# Raspberry_Pi_PCB.net
KiCad netlist of a schematic drawn in EAGLE
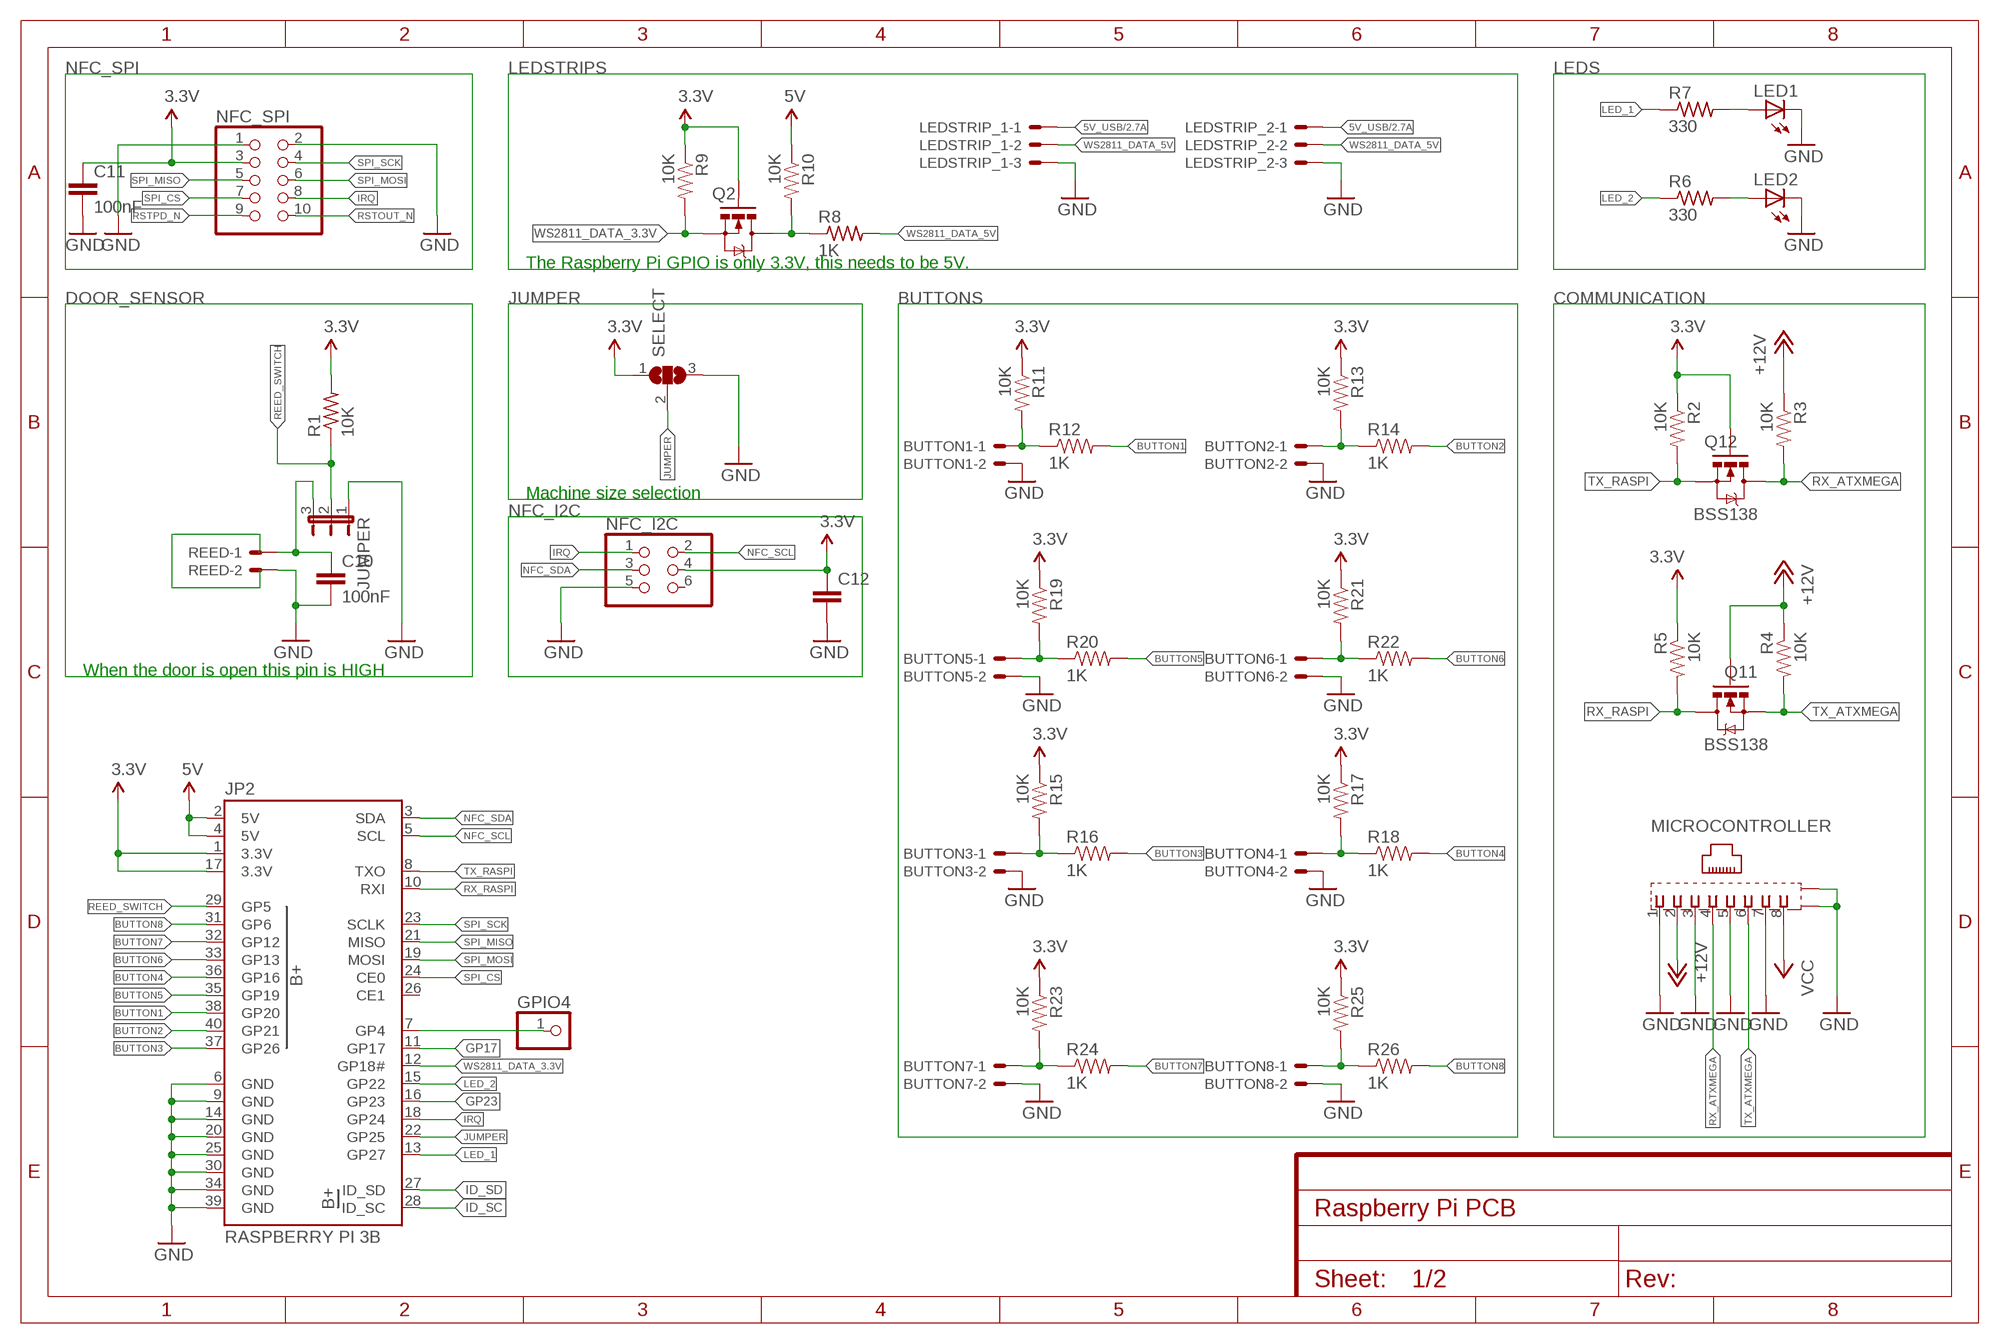
[diagram p0: schematic, sheet 1]
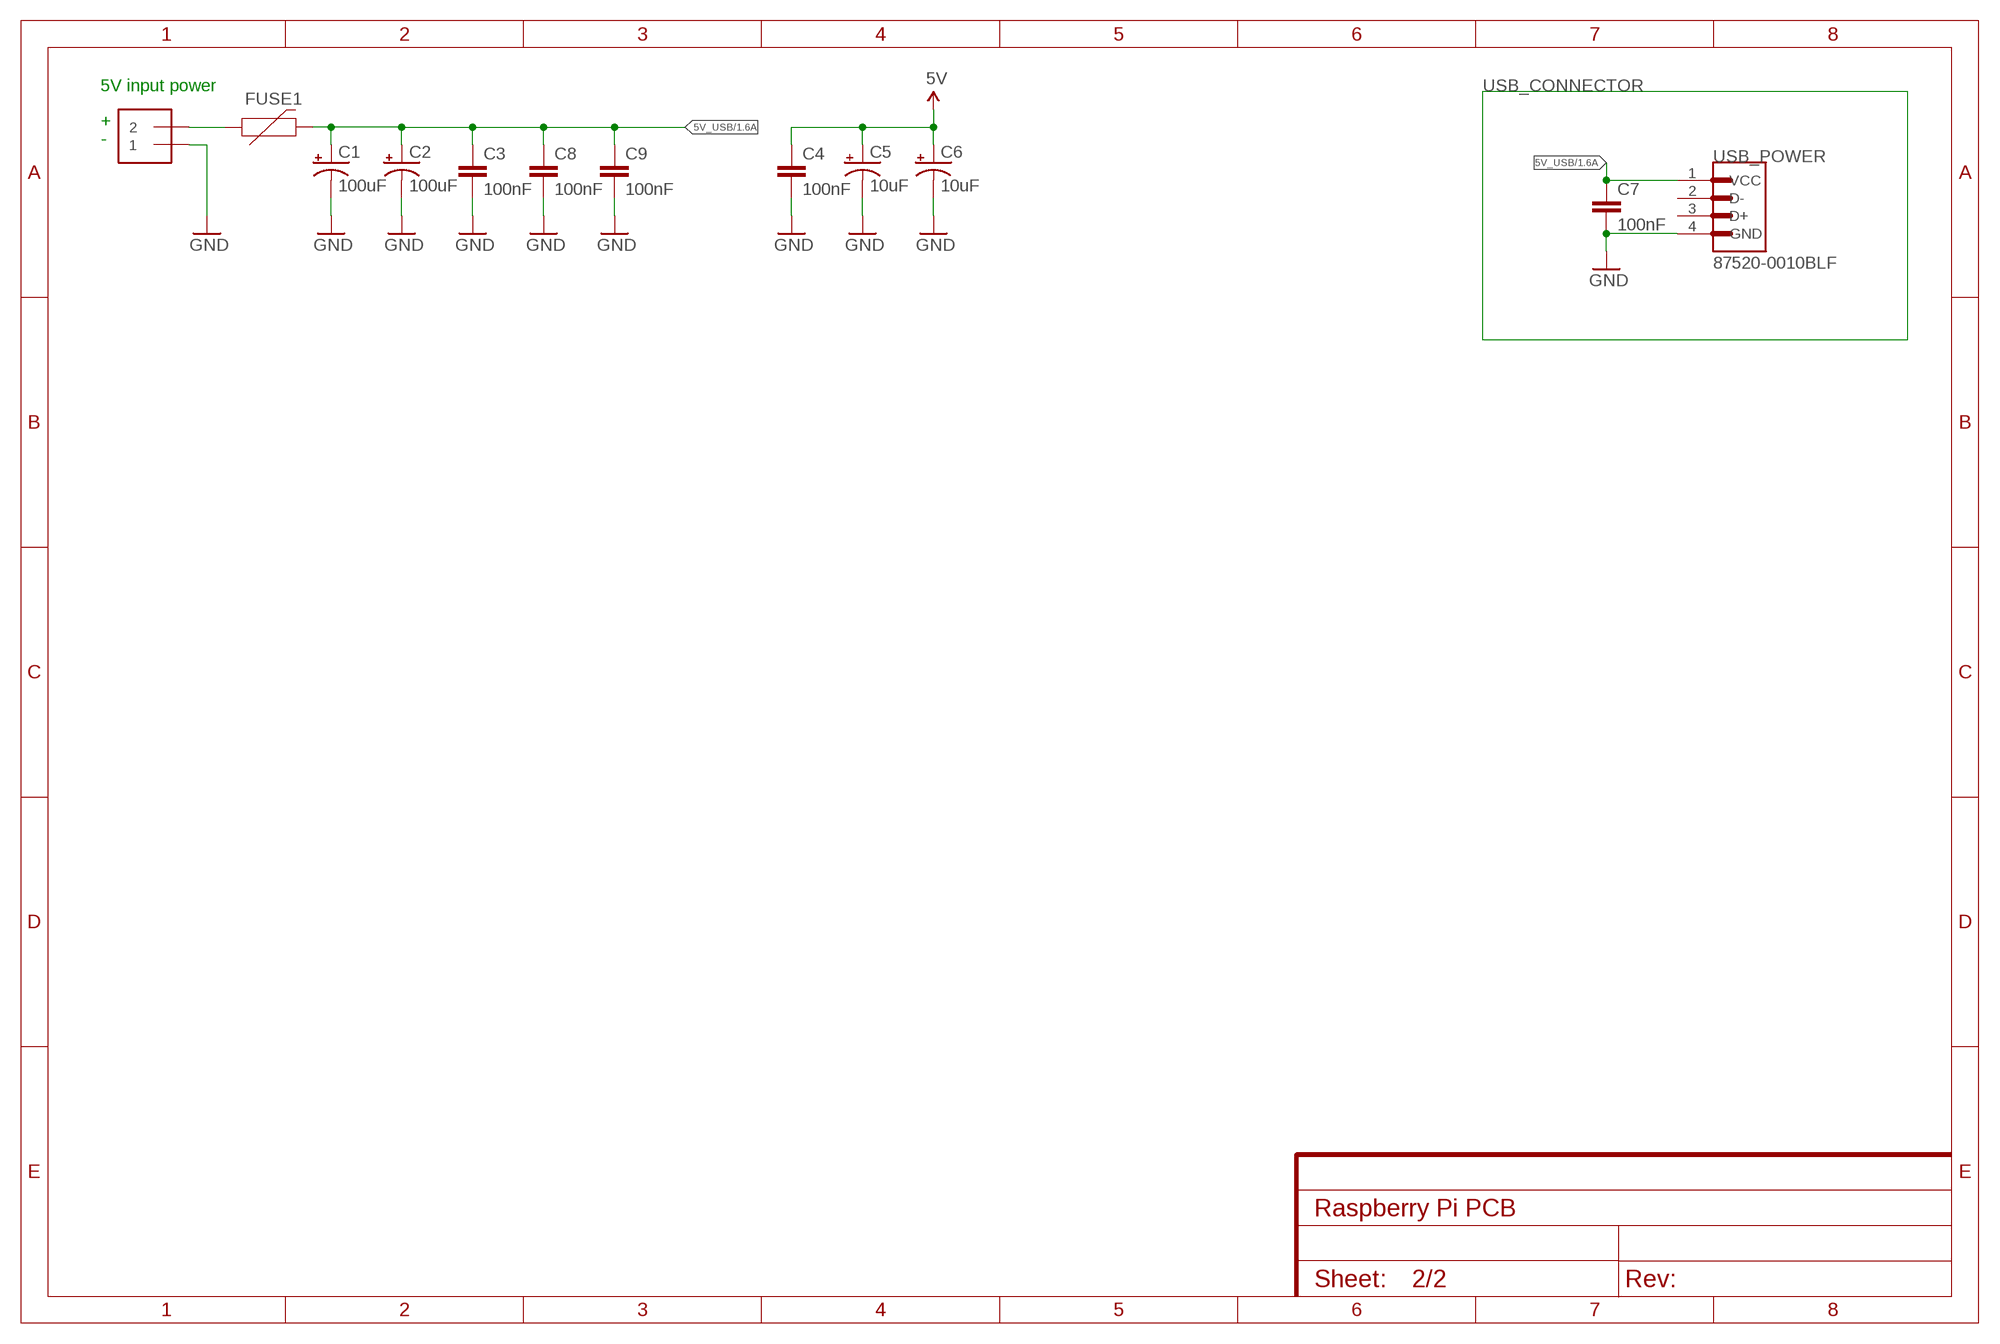
[diagram p1: schematic, sheet 2]

(export (version "E")
  (design (tool "Eeschema 10.0.6"))
  (components
    (comp (ref "BUTTON1")
      (value "22-05-7028-02")
      (footprint "eagle-import:7395-02")
      (fields (field (name "MF") "MOLEX"))
      (libsource (lib "eagle-import") (part "22-?-0205-7028"))
    )
    (comp (ref "BUTTON2")
      (value "22-05-7028-02")
      (footprint "eagle-import:7395-02")
      (fields (field (name "MF") "MOLEX"))
      (libsource (lib "eagle-import") (part "22-?-0205-7028"))
    )
    (comp (ref "BUTTON3")
      (value "22-05-7028-02")
      (footprint "eagle-import:7395-02")
      (fields (field (name "MF") "MOLEX"))
      (libsource (lib "eagle-import") (part "22-?-0205-7028"))
    )
    (comp (ref "BUTTON4")
      (value "22-05-7028-02")
      (footprint "eagle-import:7395-02")
      (fields (field (name "MF") "MOLEX"))
      (libsource (lib "eagle-import") (part "22-?-0205-7028"))
    )
    (comp (ref "BUTTON5")
      (value "22-05-7028-02")
      (footprint "eagle-import:7395-02")
      (fields (field (name "MF") "MOLEX"))
      (libsource (lib "eagle-import") (part "22-?-0205-7028"))
    )
    (comp (ref "BUTTON6")
      (value "22-05-7028-02")
      (footprint "eagle-import:7395-02")
      (fields (field (name "MF") "MOLEX"))
      (libsource (lib "eagle-import") (part "22-?-0205-7028"))
    )
    (comp (ref "BUTTON7")
      (value "22-05-7028-02")
      (footprint "eagle-import:7395-02")
      (fields (field (name "MF") "MOLEX"))
      (libsource (lib "eagle-import") (part "22-?-0205-7028"))
    )
    (comp (ref "BUTTON8")
      (value "22-05-7028-02")
      (footprint "eagle-import:7395-02")
      (fields (field (name "MF") "MOLEX"))
      (libsource (lib "eagle-import") (part "22-?-0205-7028"))
    )
    (comp (ref "C10")
      (value "100nF")
      (footprint "eagle-import:0805")
      (libsource (lib "eagle-import") (part "1.0UF-0805-25V-(+80/-20%)"))
    )
    (comp (ref "C11")
      (value "100nF")
      (footprint "eagle-import:0805")
      (libsource (lib "eagle-import") (part "1.0UF-0805-25V-(+80/-20%)"))
    )
    (comp (ref "C12")
      (value "100nF")
      (footprint "eagle-import:0805")
      (libsource (lib "eagle-import") (part "1.0UF-0805-25V-(+80/-20%)"))
    )
    (comp (ref "GPIO4")
      (value "PINHD-1X1")
      (footprint "eagle-import:1X01")
      (libsource (lib "eagle-import") (part "PINHD-1X1"))
    )
    (comp (ref "JP2")
      (value "RASPBERRY PI 3B")
      (footprint "eagle-import:2X20-SHROUDED")
      (libsource (lib "eagle-import") (part "RASPBERRYPI-B+-GPIO"))
    )
    (comp (ref "JUMPER")
      (value "JP2E")
      (footprint "eagle-import:JP2")
      (libsource (lib "eagle-import") (part "JP2E"))
    )
    (comp (ref "LED1")
      (value "LEDCHIPLED_0805")
      (footprint "eagle-import:CHIPLED_0805")
      (libsource (lib "eagle-import") (part "LEDCHIPLED_0805"))
    )
    (comp (ref "LED2")
      (value "LEDCHIPLED_0805")
      (footprint "eagle-import:CHIPLED_0805")
      (libsource (lib "eagle-import") (part "LEDCHIPLED_0805"))
    )
    (comp (ref "LEDSTRIP_1")
      (value "22-05-7038-03")
      (footprint "eagle-import:7395-03")
      (fields (field (name "MF") "MOLEX"))
      (libsource (lib "eagle-import") (part "22-?-0305-7038"))
    )
    (comp (ref "LEDSTRIP_2")
      (value "22-05-7038-03")
      (footprint "eagle-import:7395-03")
      (fields (field (name "MF") "MOLEX"))
      (libsource (lib "eagle-import") (part "22-?-0305-7038"))
    )
    (comp (ref "MICROCONTROLLER")
      (value "0446200002")
      (footprint "eagle-import:0446200002")
      (fields (field (name "MF") "MOLEX"))
      (libsource (lib "eagle-import") (part "0446200002"))
    )
    (comp (ref "NFC_I2C")
      (value "PINHD-2X3")
      (footprint "eagle-import:2X03")
      (libsource (lib "eagle-import") (part "PINHD-2X3"))
    )
    (comp (ref "NFC_SPI")
      (value "PINHD-2X5")
      (footprint "eagle-import:2X05")
      (libsource (lib "eagle-import") (part "PINHD-2X5"))
    )
    (comp (ref "Q2")
      (value "BSS138")
      (footprint "eagle-import:SOT23-3")
      (libsource (lib "eagle-import") (part "MOSFET-NCHANNELSMD"))
    )
    (comp (ref "Q11")
      (value "BSS138")
      (footprint "eagle-import:SOT23-3")
      (libsource (lib "eagle-import") (part "MOSFET-NCHANNELSMD"))
    )
    (comp (ref "Q12")
      (value "BSS138")
      (footprint "eagle-import:SOT23-3")
      (libsource (lib "eagle-import") (part "MOSFET-NCHANNELSMD"))
    )
    (comp (ref "R1")
      (value "10K")
      (footprint "eagle-import:R0805")
      (libsource (lib "eagle-import") (part "R-US_R0805"))
    )
    (comp (ref "R2")
      (value "10K")
      (footprint "eagle-import:0603-RES")
      (libsource (lib "eagle-import") (part "RESISTOR0603-RES"))
    )
    (comp (ref "R3")
      (value "10K")
      (footprint "eagle-import:0603-RES")
      (libsource (lib "eagle-import") (part "RESISTOR0603-RES"))
    )
    (comp (ref "R4")
      (value "10K")
      (footprint "eagle-import:0603-RES")
      (libsource (lib "eagle-import") (part "RESISTOR0603-RES"))
    )
    (comp (ref "R5")
      (value "10K")
      (footprint "eagle-import:0603-RES")
      (libsource (lib "eagle-import") (part "RESISTOR0603-RES"))
    )
    (comp (ref "R6")
      (value "330")
      (footprint "eagle-import:R0805")
      (libsource (lib "eagle-import") (part "R-US_R0805"))
    )
    (comp (ref "R7")
      (value "330")
      (footprint "eagle-import:R0805")
      (libsource (lib "eagle-import") (part "R-US_R0805"))
    )
    (comp (ref "R8")
      (value "1K")
      (footprint "eagle-import:R0805")
      (libsource (lib "eagle-import") (part "adafruit_420_R-US_R0805"))
    )
    (comp (ref "R9")
      (value "10K")
      (footprint "eagle-import:0603-RES")
      (libsource (lib "eagle-import") (part "RESISTOR0603-RES"))
    )
    (comp (ref "R10")
      (value "10K")
      (footprint "eagle-import:0603-RES")
      (libsource (lib "eagle-import") (part "RESISTOR0603-RES"))
    )
    (comp (ref "R11")
      (value "10K")
      (footprint "eagle-import:0603-RES")
      (libsource (lib "eagle-import") (part "RESISTOR0603-RES"))
    )
    (comp (ref "R12")
      (value "1K")
      (footprint "eagle-import:0603-RES")
      (libsource (lib "eagle-import") (part "RESISTOR0603-RES"))
    )
    (comp (ref "R13")
      (value "10K")
      (footprint "eagle-import:0603-RES")
      (libsource (lib "eagle-import") (part "RESISTOR0603-RES"))
    )
    (comp (ref "R14")
      (value "1K")
      (footprint "eagle-import:0603-RES")
      (libsource (lib "eagle-import") (part "RESISTOR0603-RES"))
    )
    (comp (ref "R15")
      (value "10K")
      (footprint "eagle-import:0603-RES")
      (libsource (lib "eagle-import") (part "RESISTOR0603-RES"))
    )
    (comp (ref "R16")
      (value "1K")
      (footprint "eagle-import:0603-RES")
      (libsource (lib "eagle-import") (part "RESISTOR0603-RES"))
    )
    (comp (ref "R17")
      (value "10K")
      (footprint "eagle-import:0603-RES")
      (libsource (lib "eagle-import") (part "RESISTOR0603-RES"))
    )
    (comp (ref "R18")
      (value "1K")
      (footprint "eagle-import:0603-RES")
      (libsource (lib "eagle-import") (part "RESISTOR0603-RES"))
    )
    (comp (ref "R19")
      (value "10K")
      (footprint "eagle-import:0603-RES")
      (libsource (lib "eagle-import") (part "RESISTOR0603-RES"))
    )
    (comp (ref "R20")
      (value "1K")
      (footprint "eagle-import:0603-RES")
      (libsource (lib "eagle-import") (part "RESISTOR0603-RES"))
    )
    (comp (ref "R21")
      (value "10K")
      (footprint "eagle-import:0603-RES")
      (libsource (lib "eagle-import") (part "RESISTOR0603-RES"))
    )
    (comp (ref "R22")
      (value "1K")
      (footprint "eagle-import:0603-RES")
      (libsource (lib "eagle-import") (part "RESISTOR0603-RES"))
    )
    (comp (ref "R23")
      (value "10K")
      (footprint "eagle-import:0603-RES")
      (libsource (lib "eagle-import") (part "RESISTOR0603-RES"))
    )
    (comp (ref "R24")
      (value "1K")
      (footprint "eagle-import:0603-RES")
      (libsource (lib "eagle-import") (part "RESISTOR0603-RES"))
    )
    (comp (ref "R25")
      (value "10K")
      (footprint "eagle-import:0603-RES")
      (libsource (lib "eagle-import") (part "RESISTOR0603-RES"))
    )
    (comp (ref "R26")
      (value "1K")
      (footprint "eagle-import:0603-RES")
      (libsource (lib "eagle-import") (part "RESISTOR0603-RES"))
    )
    (comp (ref "REED")
      (value "22-05-7028-02")
      (footprint "eagle-import:7395-02")
      (fields (field (name "MF") "MOLEX"))
      (libsource (lib "eagle-import") (part "22-?-0205-7028"))
    )
    (comp (ref "SELECT")
      (value "SJ2W")
      (footprint "eagle-import:SJ_2")
      (libsource (lib "eagle-import") (part "SJ2W"))
    )
    (comp (ref "C1")
      (value "100uF")
      (footprint "eagle-import:175TMP-0810")
      (libsource (lib "eagle-import") (part "CPOL-US175TMP-0810"))
    )
    (comp (ref "C2")
      (value "100uF")
      (footprint "eagle-import:175TMP-0810")
      (libsource (lib "eagle-import") (part "CPOL-US175TMP-0810"))
    )
    (comp (ref "C3")
      (value "100nF")
      (footprint "eagle-import:0805")
      (libsource (lib "eagle-import") (part "1.0UF-0805-25V-(+80/-20%)"))
    )
    (comp (ref "C4")
      (value "100nF")
      (footprint "eagle-import:0805")
      (libsource (lib "eagle-import") (part "1.0UF-0805-25V-(+80/-20%)"))
    )
    (comp (ref "C5")
      (value "10uF")
      (footprint "eagle-import:153CLV-0505")
      (libsource (lib "eagle-import") (part "CPOL-US153CLV-0505"))
    )
    (comp (ref "C6")
      (value "10uF")
      (footprint "eagle-import:153CLV-0505")
      (libsource (lib "eagle-import") (part "CPOL-US153CLV-0505"))
    )
    (comp (ref "C7")
      (value "100nF")
      (footprint "eagle-import:0805")
      (libsource (lib "eagle-import") (part "1.0UF-0805-25V-(+80/-20%)"))
    )
    (comp (ref "C8")
      (value "100nF")
      (footprint "eagle-import:0805")
      (libsource (lib "eagle-import") (part "1.0UF-0805-25V-(+80/-20%)"))
    )
    (comp (ref "C9")
      (value "100nF")
      (footprint "eagle-import:0805")
      (libsource (lib "eagle-import") (part "1.0UF-0805-25V-(+80/-20%)"))
    )
    (comp (ref "FUSE1")
      (value "6V/0.5A")
      (footprint "eagle-import:1206")
      (libsource (lib "eagle-import") (part "PPTC_HALF-AMP"))
    )
    (comp (ref "INPUT")
      (value "1X2-3.5MM")
      (footprint "eagle-import:1X2-3.5MM")
      (libsource (lib "eagle-import") (part "1X2-3.5MM"))
    )
    (comp (ref "USB_POWER")
      (value "87520-0010BLF")
      (footprint "eagle-import:FCI_87520-0010BLF")
      (fields (field (name "DIGI-KEY_PART_NUMBER") "609-1045-ND") (field (name "MF") "Amphenol ICC"))
      (libsource (lib "eagle-import") (part "87520-0010BLF"))
    )
  )
  (nets
    (net (code "1") (name "+12V") (class "Default")
      (node (ref "MICROCONTROLLER") (pin "2") (pinfunction "2_2") (pintype "passive"))
      (node (ref "Q11") (pin "1") (pinfunction "G_1") (pintype "passive"))
      (node (ref "R3") (pin "1") (pinfunction "1_1") (pintype "passive"))
      (node (ref "R4") (pin "1") (pinfunction "1_1") (pintype "passive"))
    )
    (net (code "2") (name "3.3V") (class "Default")
      (node (ref "C11") (pin "1") (pinfunction "1_1") (pintype "passive"))
      (node (ref "C12") (pin "1") (pinfunction "1_1") (pintype "passive"))
      (node (ref "JP2") (pin "1") (pinfunction "3.3V_1") (pintype "power_in"))
      (node (ref "JP2") (pin "17") (pinfunction "3.3V_17") (pintype "power_in"))
      (node (ref "NFC_I2C") (pin "4") (pinfunction "4_4") (pintype "passive"))
      (node (ref "NFC_SPI") (pin "3") (pinfunction "3_3") (pintype "passive"))
      (node (ref "Q12") (pin "1") (pinfunction "G_1") (pintype "passive"))
      (node (ref "Q2") (pin "1") (pinfunction "G_1") (pintype "passive"))
      (node (ref "R1") (pin "2") (pinfunction "2_2") (pintype "passive"))
      (node (ref "R11") (pin "1") (pinfunction "1_1") (pintype "passive"))
      (node (ref "R13") (pin "1") (pinfunction "1_1") (pintype "passive"))
      (node (ref "R15") (pin "1") (pinfunction "1_1") (pintype "passive"))
      (node (ref "R17") (pin "1") (pinfunction "1_1") (pintype "passive"))
      (node (ref "R19") (pin "1") (pinfunction "1_1") (pintype "passive"))
      (node (ref "R2") (pin "1") (pinfunction "1_1") (pintype "passive"))
      (node (ref "R21") (pin "1") (pinfunction "1_1") (pintype "passive"))
      (node (ref "R23") (pin "1") (pinfunction "1_1") (pintype "passive"))
      (node (ref "R25") (pin "1") (pinfunction "1_1") (pintype "passive"))
      (node (ref "R5") (pin "1") (pinfunction "1_1") (pintype "passive"))
      (node (ref "R9") (pin "1") (pinfunction "1_1") (pintype "passive"))
      (node (ref "SELECT") (pin "1") (pinfunction "1_1") (pintype "passive"))
    )
    (net (code "3") (name "5V") (class "Default")
      (node (ref "C4") (pin "1") (pinfunction "1_1") (pintype "passive"))
      (node (ref "C5") (pin "+") (pinfunction "+_+") (pintype "passive"))
      (node (ref "C6") (pin "+") (pinfunction "+_+") (pintype "passive"))
      (node (ref "JP2") (pin "2") (pinfunction "5V_2") (pintype "power_in"))
      (node (ref "JP2") (pin "4") (pinfunction "5V_4") (pintype "power_in"))
      (node (ref "R10") (pin "1") (pinfunction "1_1") (pintype "passive"))
    )
    (net (code "4") (name "5V_USB") (class "Default")
      (node (ref "C1") (pin "+") (pinfunction "+_+") (pintype "passive"))
      (node (ref "C2") (pin "+") (pinfunction "+_+") (pintype "passive"))
      (node (ref "C3") (pin "1") (pinfunction "1_1") (pintype "passive"))
      (node (ref "C7") (pin "1") (pinfunction "1_1") (pintype "passive"))
      (node (ref "C8") (pin "1") (pinfunction "1_1") (pintype "passive"))
      (node (ref "C9") (pin "1") (pinfunction "1_1") (pintype "passive"))
      (node (ref "FUSE1") (pin "2") (pinfunction "2_2") (pintype "bidirectional"))
      (node (ref "LEDSTRIP_1") (pin "1") (pinfunction "S_1") (pintype "passive"))
      (node (ref "LEDSTRIP_2") (pin "1") (pinfunction "S_1") (pintype "passive"))
      (node (ref "USB_POWER") (pin "1") (pinfunction "VCC_1") (pintype "power_in"))
    )
    (net (code "5") (name "BUTTON1") (class "Default")
      (node (ref "JP2") (pin "38") (pinfunction "GP20_38") (pintype "bidirectional"))
      (node (ref "R12") (pin "2") (pinfunction "2_2") (pintype "passive"))
    )
    (net (code "6") (name "BUTTON2") (class "Default")
      (node (ref "JP2") (pin "40") (pinfunction "GP21_40") (pintype "bidirectional"))
      (node (ref "R14") (pin "2") (pinfunction "2_2") (pintype "passive"))
    )
    (net (code "7") (name "BUTTON3") (class "Default")
      (node (ref "JP2") (pin "37") (pinfunction "GP26_37") (pintype "bidirectional"))
      (node (ref "R16") (pin "2") (pinfunction "2_2") (pintype "passive"))
    )
    (net (code "8") (name "BUTTON4") (class "Default")
      (node (ref "JP2") (pin "36") (pinfunction "GP16_36") (pintype "bidirectional"))
      (node (ref "R18") (pin "2") (pinfunction "2_2") (pintype "passive"))
    )
    (net (code "9") (name "BUTTON5") (class "Default")
      (node (ref "JP2") (pin "35") (pinfunction "GP19_35") (pintype "bidirectional"))
      (node (ref "R20") (pin "2") (pinfunction "2_2") (pintype "passive"))
    )
    (net (code "10") (name "BUTTON6") (class "Default")
      (node (ref "JP2") (pin "33") (pinfunction "GP13_33") (pintype "bidirectional"))
      (node (ref "R22") (pin "2") (pinfunction "2_2") (pintype "passive"))
    )
    (net (code "11") (name "BUTTON7") (class "Default")
      (node (ref "JP2") (pin "32") (pinfunction "GP12_32") (pintype "bidirectional"))
      (node (ref "R24") (pin "2") (pinfunction "2_2") (pintype "passive"))
    )
    (net (code "12") (name "BUTTON8") (class "Default")
      (node (ref "JP2") (pin "31") (pinfunction "GP6_31") (pintype "bidirectional"))
      (node (ref "R26") (pin "2") (pinfunction "2_2") (pintype "passive"))
    )
    (net (code "16") (name "GND") (class "Default")
      (node (ref "BUTTON1") (pin "2") (pinfunction "S_2") (pintype "passive"))
      (node (ref "BUTTON2") (pin "2") (pinfunction "S_2") (pintype "passive"))
      (node (ref "BUTTON3") (pin "2") (pinfunction "S_2") (pintype "passive"))
      (node (ref "BUTTON4") (pin "2") (pinfunction "S_2") (pintype "passive"))
      (node (ref "BUTTON5") (pin "2") (pinfunction "S_2") (pintype "passive"))
      (node (ref "BUTTON6") (pin "2") (pinfunction "S_2") (pintype "passive"))
      (node (ref "BUTTON7") (pin "2") (pinfunction "S_2") (pintype "passive"))
      (node (ref "BUTTON8") (pin "2") (pinfunction "S_2") (pintype "passive"))
      (node (ref "C1") (pin "-") (pinfunction "-_-") (pintype "passive"))
      (node (ref "C10") (pin "2") (pinfunction "2_2") (pintype "passive"))
      (node (ref "C11") (pin "2") (pinfunction "2_2") (pintype "passive"))
      (node (ref "C12") (pin "2") (pinfunction "2_2") (pintype "passive"))
      (node (ref "C2") (pin "-") (pinfunction "-_-") (pintype "passive"))
      (node (ref "C3") (pin "2") (pinfunction "2_2") (pintype "passive"))
      (node (ref "C4") (pin "2") (pinfunction "2_2") (pintype "passive"))
      (node (ref "C5") (pin "-") (pinfunction "-_-") (pintype "passive"))
      (node (ref "C6") (pin "-") (pinfunction "-_-") (pintype "passive"))
      (node (ref "C7") (pin "2") (pinfunction "2_2") (pintype "passive"))
      (node (ref "C8") (pin "2") (pinfunction "2_2") (pintype "passive"))
      (node (ref "C9") (pin "2") (pinfunction "2_2") (pintype "passive"))
      (node (ref "INPUT") (pin "1") (pinfunction "1_1") (pintype "passive"))
      (node (ref "JP2") (pin "14") (pinfunction "GND_14") (pintype "power_in"))
      (node (ref "JP2") (pin "20") (pinfunction "GND_20") (pintype "power_in"))
      (node (ref "JP2") (pin "25") (pinfunction "GND_25") (pintype "power_in"))
      (node (ref "JP2") (pin "30") (pinfunction "GND_30") (pintype "power_in"))
      (node (ref "JP2") (pin "34") (pinfunction "GND_34") (pintype "power_in"))
      (node (ref "JP2") (pin "39") (pinfunction "GND_39") (pintype "power_in"))
      (node (ref "JP2") (pin "6") (pinfunction "GND_6") (pintype "power_in"))
      (node (ref "JP2") (pin "9") (pinfunction "GND_9") (pintype "power_in"))
      (node (ref "JUMPER") (pin "1") (pinfunction "1_1") (pintype "passive"))
      (node (ref "LED1") (pin "C") (pinfunction "C_C") (pintype "passive"))
      (node (ref "LED2") (pin "C") (pinfunction "C_C") (pintype "passive"))
      (node (ref "LEDSTRIP_1") (pin "3") (pinfunction "S_3") (pintype "passive"))
      (node (ref "LEDSTRIP_2") (pin "3") (pinfunction "S_3") (pintype "passive"))
      (node (ref "MICROCONTROLLER") (pin "1") (pinfunction "1_1") (pintype "passive"))
      (node (ref "MICROCONTROLLER") (pin "3") (pinfunction "3_3") (pintype "passive"))
      (node (ref "MICROCONTROLLER") (pin "5") (pinfunction "5_5") (pintype "passive"))
      (node (ref "MICROCONTROLLER") (pin "7") (pinfunction "7_7") (pintype "passive"))
      (node (ref "MICROCONTROLLER") (pin "S@1") (pinfunction "S1_S@1") (pintype "passive"))
      (node (ref "MICROCONTROLLER") (pin "S@2") (pinfunction "S2_S@2") (pintype "passive"))
      (node (ref "NFC_I2C") (pin "5") (pinfunction "5_5") (pintype "passive"))
      (node (ref "NFC_SPI") (pin "1") (pinfunction "1_1") (pintype "passive"))
      (node (ref "NFC_SPI") (pin "2") (pinfunction "2_2") (pintype "passive"))
      (node (ref "REED") (pin "2") (pinfunction "S_2") (pintype "passive"))
      (node (ref "SELECT") (pin "3") (pinfunction "3_3") (pintype "passive"))
      (node (ref "USB_POWER") (pin "4") (pinfunction "GND_4") (pintype "power_in"))
    )
    (net (code "17") (name "GP17") (class "Default")
      (node (ref "JP2") (pin "11") (pinfunction "GP17_11") (pintype "bidirectional"))
    )
    (net (code "18") (name "GP23") (class "Default")
      (node (ref "JP2") (pin "16") (pinfunction "GP23_16") (pintype "bidirectional"))
    )
    (net (code "19") (name "ID_SC") (class "Default")
      (node (ref "JP2") (pin "28") (pinfunction "ID_SC_28") (pintype "bidirectional"))
    )
    (net (code "20") (name "ID_SD") (class "Default")
      (node (ref "JP2") (pin "27") (pinfunction "ID_SD_27") (pintype "bidirectional"))
    )
    (net (code "21") (name "IRQ") (class "Default")
      (node (ref "JP2") (pin "18") (pinfunction "GP24_18") (pintype "bidirectional"))
      (node (ref "NFC_I2C") (pin "1") (pinfunction "1_1") (pintype "passive"))
      (node (ref "NFC_SPI") (pin "8") (pinfunction "8_8") (pintype "passive"))
    )
    (net (code "22") (name "JUMPER") (class "Default")
      (node (ref "JP2") (pin "22") (pinfunction "GP25_22") (pintype "bidirectional"))
      (node (ref "SELECT") (pin "2") (pinfunction "2_2") (pintype "passive"))
    )
    (net (code "25") (name "LED_1") (class "Default")
      (node (ref "JP2") (pin "13") (pinfunction "GP27_13") (pintype "bidirectional"))
      (node (ref "R7") (pin "1") (pinfunction "1_1") (pintype "passive"))
    )
    (net (code "26") (name "LED_2") (class "Default")
      (node (ref "JP2") (pin "15") (pinfunction "GP22_15") (pintype "bidirectional"))
      (node (ref "R6") (pin "1") (pinfunction "1_1") (pintype "passive"))
    )
    (net (code "28") (name "NFC_SCL") (class "Default")
      (node (ref "JP2") (pin "5") (pinfunction "SCL_5") (pintype "bidirectional"))
      (node (ref "NFC_I2C") (pin "2") (pinfunction "2_2") (pintype "passive"))
    )
    (net (code "29") (name "NFC_SDA") (class "Default")
      (node (ref "JP2") (pin "3") (pinfunction "SDA_3") (pintype "bidirectional"))
      (node (ref "NFC_I2C") (pin "3") (pinfunction "3_3") (pintype "passive"))
    )
    (net (code "31") (name "Net-(BUTTON1A-S)") (class "Default")
      (node (ref "BUTTON1") (pin "1") (pinfunction "S_1") (pintype "passive"))
      (node (ref "R11") (pin "2") (pinfunction "2_2") (pintype "passive"))
      (node (ref "R12") (pin "1") (pinfunction "1_1") (pintype "passive"))
    )
    (net (code "32") (name "Net-(BUTTON2A-S)") (class "Default")
      (node (ref "BUTTON2") (pin "1") (pinfunction "S_1") (pintype "passive"))
      (node (ref "R13") (pin "2") (pinfunction "2_2") (pintype "passive"))
      (node (ref "R14") (pin "1") (pinfunction "1_1") (pintype "passive"))
    )
    (net (code "33") (name "Net-(BUTTON3A-S)") (class "Default")
      (node (ref "BUTTON3") (pin "1") (pinfunction "S_1") (pintype "passive"))
      (node (ref "R15") (pin "2") (pinfunction "2_2") (pintype "passive"))
      (node (ref "R16") (pin "1") (pinfunction "1_1") (pintype "passive"))
    )
    (net (code "34") (name "Net-(BUTTON4A-S)") (class "Default")
      (node (ref "BUTTON4") (pin "1") (pinfunction "S_1") (pintype "passive"))
      (node (ref "R17") (pin "2") (pinfunction "2_2") (pintype "passive"))
      (node (ref "R18") (pin "1") (pinfunction "1_1") (pintype "passive"))
    )
    (net (code "35") (name "Net-(BUTTON5A-S)") (class "Default")
      (node (ref "BUTTON5") (pin "1") (pinfunction "S_1") (pintype "passive"))
      (node (ref "R19") (pin "2") (pinfunction "2_2") (pintype "passive"))
      (node (ref "R20") (pin "1") (pinfunction "1_1") (pintype "passive"))
    )
    (net (code "36") (name "Net-(BUTTON6A-S)") (class "Default")
      (node (ref "BUTTON6") (pin "1") (pinfunction "S_1") (pintype "passive"))
      (node (ref "R21") (pin "2") (pinfunction "2_2") (pintype "passive"))
      (node (ref "R22") (pin "1") (pinfunction "1_1") (pintype "passive"))
    )
    (net (code "37") (name "Net-(BUTTON7A-S)") (class "Default")
      (node (ref "BUTTON7") (pin "1") (pinfunction "S_1") (pintype "passive"))
      (node (ref "R23") (pin "2") (pinfunction "2_2") (pintype "passive"))
      (node (ref "R24") (pin "1") (pinfunction "1_1") (pintype "passive"))
    )
    (net (code "38") (name "Net-(BUTTON8A-S)") (class "Default")
      (node (ref "BUTTON8") (pin "1") (pinfunction "S_1") (pintype "passive"))
      (node (ref "R25") (pin "2") (pinfunction "2_2") (pintype "passive"))
      (node (ref "R26") (pin "1") (pinfunction "1_1") (pintype "passive"))
    )
    (net (code "39") (name "Net-(FUSE1-Pad1)") (class "Default")
      (node (ref "FUSE1") (pin "1") (pinfunction "1_1") (pintype "bidirectional"))
      (node (ref "INPUT") (pin "2") (pinfunction "2_2") (pintype "passive"))
    )
    (net (code "40") (name "Net-(JP2-GP4)") (class "Default")
      (node (ref "GPIO4") (pin "1") (pinfunction "1_1") (pintype "passive"))
      (node (ref "JP2") (pin "7") (pinfunction "GP4_7") (pintype "bidirectional"))
    )
    (net (code "41") (name "Net-(LED1-PadA)") (class "Default")
      (node (ref "LED1") (pin "A") (pinfunction "A_A") (pintype "passive"))
      (node (ref "R7") (pin "2") (pinfunction "2_2") (pintype "passive"))
    )
    (net (code "42") (name "Net-(LED2-PadA)") (class "Default")
      (node (ref "LED2") (pin "A") (pinfunction "A_A") (pintype "passive"))
      (node (ref "R6") (pin "2") (pinfunction "2_2") (pintype "passive"))
    )
    (net (code "43") (name "Net-(Q2-D)") (class "Default")
      (node (ref "Q2") (pin "3") (pinfunction "D_3") (pintype "passive"))
      (node (ref "R10") (pin "2") (pinfunction "2_2") (pintype "passive"))
      (node (ref "R8") (pin "1") (pinfunction "1_1") (pintype "passive"))
    )
    (net (code "44") (name "Net-(REEDA-S)") (class "Default")
      (node (ref "C10") (pin "1") (pinfunction "1_1") (pintype "passive"))
      (node (ref "JUMPER") (pin "3") (pinfunction "3_3") (pintype "passive"))
      (node (ref "REED") (pin "1") (pinfunction "S_1") (pintype "passive"))
    )
    (net (code "45") (name "REED_SWITCH") (class "Default")
      (node (ref "JP2") (pin "29") (pinfunction "GP5_29") (pintype "bidirectional"))
      (node (ref "JUMPER") (pin "2") (pinfunction "2_2") (pintype "passive"))
      (node (ref "R1") (pin "1") (pinfunction "1_1") (pintype "passive"))
    )
    (net (code "46") (name "RSTOUT_N") (class "Default")
      (node (ref "NFC_SPI") (pin "10") (pinfunction "10_10") (pintype "passive"))
    )
    (net (code "47") (name "RSTPD_N") (class "Default")
      (node (ref "NFC_SPI") (pin "9") (pinfunction "9_9") (pintype "passive"))
    )
    (net (code "48") (name "RX_ATXMEGA") (class "Default")
      (node (ref "MICROCONTROLLER") (pin "4") (pinfunction "4_4") (pintype "passive"))
      (node (ref "Q12") (pin "3") (pinfunction "D_3") (pintype "passive"))
      (node (ref "R3") (pin "2") (pinfunction "2_2") (pintype "passive"))
    )
    (net (code "49") (name "RX_RASPI") (class "Default")
      (node (ref "JP2") (pin "10") (pinfunction "RXI_10") (pintype "input"))
      (node (ref "Q11") (pin "3") (pinfunction "D_3") (pintype "passive"))
      (node (ref "R5") (pin "2") (pinfunction "2_2") (pintype "passive"))
    )
    (net (code "50") (name "SPI_CS") (class "Default")
      (node (ref "JP2") (pin "24") (pinfunction "CE0_24") (pintype "output"))
      (node (ref "NFC_SPI") (pin "7") (pinfunction "7_7") (pintype "passive"))
    )
    (net (code "51") (name "SPI_MISO") (class "Default")
      (node (ref "JP2") (pin "21") (pinfunction "MISO_21") (pintype "input"))
      (node (ref "NFC_SPI") (pin "5") (pinfunction "5_5") (pintype "passive"))
    )
    (net (code "52") (name "SPI_MOSI") (class "Default")
      (node (ref "JP2") (pin "19") (pinfunction "MOSI_19") (pintype "output"))
      (node (ref "NFC_SPI") (pin "6") (pinfunction "6_6") (pintype "passive"))
    )
    (net (code "53") (name "SPI_SCK") (class "Default")
      (node (ref "JP2") (pin "23") (pinfunction "SCLK_23") (pintype "output"))
      (node (ref "NFC_SPI") (pin "4") (pinfunction "4_4") (pintype "passive"))
    )
    (net (code "54") (name "TX_ATXMEGA") (class "Default")
      (node (ref "MICROCONTROLLER") (pin "6") (pinfunction "6_6") (pintype "passive"))
      (node (ref "Q11") (pin "2") (pinfunction "S_2") (pintype "passive"))
      (node (ref "R4") (pin "2") (pinfunction "2_2") (pintype "passive"))
    )
    (net (code "55") (name "TX_RASPI") (class "Default")
      (node (ref "JP2") (pin "8") (pinfunction "TXO_8") (pintype "output"))
      (node (ref "Q12") (pin "2") (pinfunction "S_2") (pintype "passive"))
      (node (ref "R2") (pin "2") (pinfunction "2_2") (pintype "passive"))
    )
    (net (code "57") (name "VCC") (class "Default")
      (node (ref "MICROCONTROLLER") (pin "8") (pinfunction "8_8") (pintype "passive"))
    )
    (net (code "58") (name "WS2811_DATA_3.3V") (class "Default")
      (node (ref "JP2") (pin "12") (pinfunction "GP18#_12") (pintype "bidirectional"))
      (node (ref "Q2") (pin "2") (pinfunction "S_2") (pintype "passive"))
      (node (ref "R9") (pin "2") (pinfunction "2_2") (pintype "passive"))
    )
    (net (code "59") (name "WS2811_DATA_5V") (class "Default")
      (node (ref "LEDSTRIP_1") (pin "2") (pinfunction "S_2") (pintype "passive"))
      (node (ref "LEDSTRIP_2") (pin "2") (pinfunction "S_2") (pintype "passive"))
      (node (ref "R8") (pin "2") (pinfunction "2_2") (pintype "passive"))
    )
    (net (code "60") (name "unconnected-(JP2-CE1-Pad26)") (class "Default")
      (node (ref "JP2") (pin "26") (pinfunction "CE1_26") (pintype "output"))
    )
    (net (code "61") (name "unconnected-(NFC_I2C-Pad6)") (class "Default")
      (node (ref "NFC_I2C") (pin "6") (pinfunction "6_6") (pintype "passive"))
    )
    (net (code "62") (name "unconnected-(USB_POWER-D+-Pad3)") (class "Default")
      (node (ref "USB_POWER") (pin "3") (pinfunction "D+_3") (pintype "bidirectional"))
    )
    (net (code "63") (name "unconnected-(USB_POWER-D--Pad2)") (class "Default")
      (node (ref "USB_POWER") (pin "2") (pinfunction "D-_2") (pintype "bidirectional"))
    )
  )
)
